# 25k80.net
KiCad netlist of a schematic drawn in EAGLE
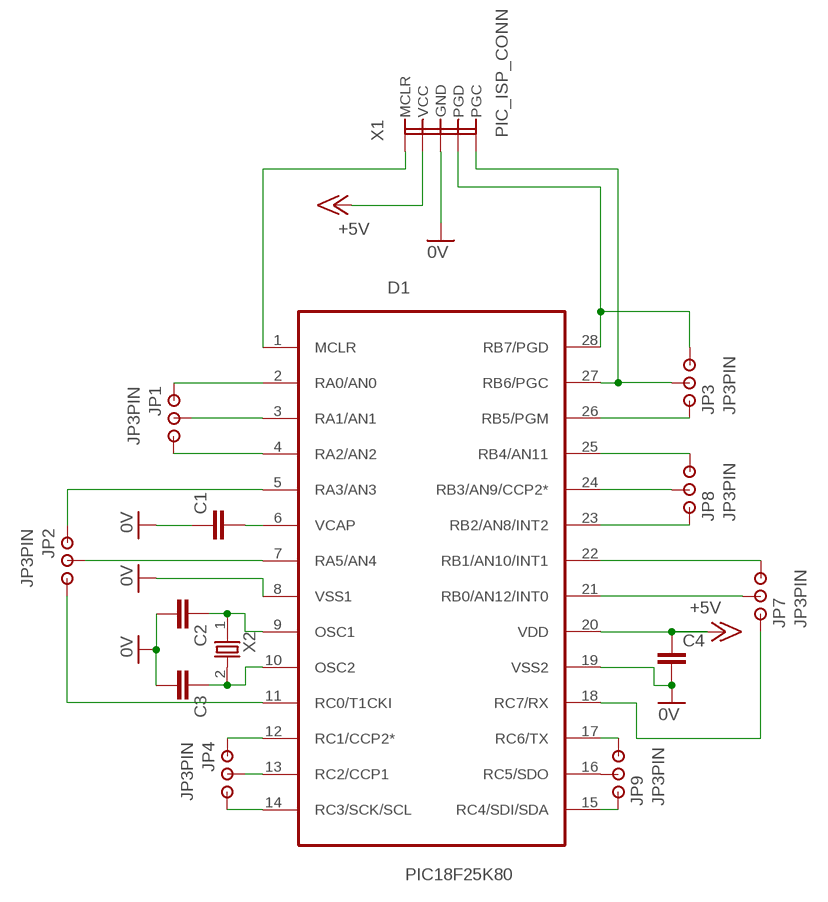
[diagram p0: schematic, sheet 1]

(export (version "E")
  (design (tool "Eeschema 10.0.6"))
  (components
    (comp (ref "C1")
      (value "C0805")
      (footprint "eagle-import:C0805D")
      (libsource (lib "eagle-import") (part "C0805"))
    )
    (comp (ref "C2")
      (value "C0805")
      (footprint "eagle-import:C0805D")
      (libsource (lib "eagle-import") (part "C0805"))
    )
    (comp (ref "C3")
      (value "C0805")
      (footprint "eagle-import:C0805D")
      (libsource (lib "eagle-import") (part "C0805"))
    )
    (comp (ref "C4")
      (value "C0805")
      (footprint "eagle-import:C0805D")
      (libsource (lib "eagle-import") (part "C0805"))
    )
    (comp (ref "D1")
      (value "PIC18F25K80")
      (footprint "eagle-import:SO-28W")
      (libsource (lib "eagle-import") (part "PIC18F25K80"))
    )
    (comp (ref "JP1")
      (value "JP3PIN")
      (footprint "eagle-import:PLC-3PIN")
      (libsource (lib "eagle-import") (part "JP3PIN"))
    )
    (comp (ref "JP2")
      (value "JP3PIN")
      (footprint "eagle-import:PLC-3PIN")
      (libsource (lib "eagle-import") (part "JP3PIN"))
    )
    (comp (ref "JP3")
      (value "JP3PIN")
      (footprint "eagle-import:PLC-3PIN")
      (libsource (lib "eagle-import") (part "JP3PIN"))
    )
    (comp (ref "JP4")
      (value "JP3PIN")
      (footprint "eagle-import:PLC-3PIN")
      (libsource (lib "eagle-import") (part "JP3PIN"))
    )
    (comp (ref "JP7")
      (value "JP3PIN")
      (footprint "eagle-import:PLC-3PIN")
      (libsource (lib "eagle-import") (part "JP3PIN"))
    )
    (comp (ref "JP8")
      (value "JP3PIN")
      (footprint "eagle-import:PLC-3PIN")
      (libsource (lib "eagle-import") (part "JP3PIN"))
    )
    (comp (ref "JP9")
      (value "JP3PIN")
      (footprint "eagle-import:PLC-3PIN")
      (libsource (lib "eagle-import") (part "JP3PIN"))
    )
    (comp (ref "X1")
      (value "PIC_ISP_CONN")
      (footprint "eagle-import:PLC-5PIN")
      (libsource (lib "eagle-import") (part "PIC_ISP_CONN"))
    )
    (comp (ref "X2")
      (value "HC49/S")
      (footprint "eagle-import:HC49_S")
      (libsource (lib "eagle-import") (part "HC49/S"))
    )
  )
  (nets
    (net (code "1") (name "+5V") (class "Default")
      (node (ref "C4") (pin "1") (pinfunction "1_1") (pintype "passive"))
      (node (ref "D1") (pin "20") (pinfunction "VDD_20") (pintype "bidirectional"))
      (node (ref "X1") (pin "P$2") (pinfunction "VCC_P$2") (pintype "bidirectional"))
    )
    (net (code "2") (name "0V") (class "Default")
      (node (ref "C1") (pin "1") (pinfunction "1_1") (pintype "passive"))
      (node (ref "C2") (pin "2") (pinfunction "2_2") (pintype "passive"))
      (node (ref "C3") (pin "2") (pinfunction "2_2") (pintype "passive"))
      (node (ref "C4") (pin "2") (pinfunction "2_2") (pintype "passive"))
      (node (ref "D1") (pin "19") (pinfunction "VSS2_19") (pintype "bidirectional"))
      (node (ref "D1") (pin "8") (pinfunction "VSS1_8") (pintype "bidirectional"))
      (node (ref "X1") (pin "P$3") (pinfunction "GND_P$3") (pintype "bidirectional"))
    )
    (net (code "3") (name "Net-(D1-MCLR)") (class "Default")
      (node (ref "D1") (pin "1") (pinfunction "MCLR_1") (pintype "bidirectional"))
      (node (ref "X1") (pin "P$1") (pinfunction "MCLR_P$1") (pintype "bidirectional"))
    )
    (net (code "4") (name "Net-(D1-OSC1)") (class "Default")
      (node (ref "C2") (pin "1") (pinfunction "1_1") (pintype "passive"))
      (node (ref "D1") (pin "9") (pinfunction "OSC1_9") (pintype "bidirectional"))
      (node (ref "X2") (pin "1") (pinfunction "1_1") (pintype "passive"))
    )
    (net (code "5") (name "Net-(D1-OSC2)") (class "Default")
      (node (ref "C3") (pin "1") (pinfunction "1_1") (pintype "passive"))
      (node (ref "D1") (pin "10") (pinfunction "OSC2_10") (pintype "bidirectional"))
      (node (ref "X2") (pin "2") (pinfunction "2_2") (pintype "passive"))
    )
    (net (code "6") (name "Net-(D1-RA0{slash}AN0)") (class "Default")
      (node (ref "D1") (pin "2") (pinfunction "RA0/AN0_2") (pintype "bidirectional"))
      (node (ref "JP1") (pin "P$1") (pinfunction "P$1_P$1") (pintype "bidirectional"))
    )
    (net (code "7") (name "Net-(D1-RA1{slash}AN1)") (class "Default")
      (node (ref "D1") (pin "3") (pinfunction "RA1/AN1_3") (pintype "bidirectional"))
      (node (ref "JP1") (pin "P$2") (pinfunction "P$2_P$2") (pintype "bidirectional"))
    )
    (net (code "8") (name "Net-(D1-RA2{slash}AN2)") (class "Default")
      (node (ref "D1") (pin "4") (pinfunction "RA2/AN2_4") (pintype "bidirectional"))
      (node (ref "JP1") (pin "P$3") (pinfunction "P$3_P$3") (pintype "bidirectional"))
    )
    (net (code "9") (name "Net-(D1-RA3{slash}AN3)") (class "Default")
      (node (ref "D1") (pin "5") (pinfunction "RA3/AN3_5") (pintype "bidirectional"))
      (node (ref "JP2") (pin "P$1") (pinfunction "P$1_P$1") (pintype "bidirectional"))
    )
    (net (code "10") (name "Net-(D1-RA5{slash}AN4)") (class "Default")
      (node (ref "D1") (pin "7") (pinfunction "RA5/AN4_7") (pintype "bidirectional"))
      (node (ref "JP2") (pin "P$2") (pinfunction "P$2_P$2") (pintype "bidirectional"))
    )
    (net (code "11") (name "Net-(D1-RB0{slash}AN12{slash}INT0)") (class "Default")
      (node (ref "D1") (pin "21") (pinfunction "RB0/AN12/INT0_21") (pintype "bidirectional"))
      (node (ref "JP7") (pin "P$2") (pinfunction "P$2_P$2") (pintype "bidirectional"))
    )
    (net (code "12") (name "Net-(D1-RB1{slash}AN10{slash}INT1)") (class "Default")
      (node (ref "D1") (pin "22") (pinfunction "RB1/AN10/INT1_22") (pintype "bidirectional"))
      (node (ref "JP7") (pin "P$3") (pinfunction "P$3_P$3") (pintype "bidirectional"))
    )
    (net (code "13") (name "Net-(D1-RB2{slash}AN8{slash}INT2)") (class "Default")
      (node (ref "D1") (pin "23") (pinfunction "RB2/AN8/INT2_23") (pintype "bidirectional"))
      (node (ref "JP8") (pin "P$1") (pinfunction "P$1_P$1") (pintype "bidirectional"))
    )
    (net (code "14") (name "Net-(D1-RB3{slash}AN9{slash}CCP2*)") (class "Default")
      (node (ref "D1") (pin "24") (pinfunction "RB3/AN9/CCP2*_24") (pintype "bidirectional"))
      (node (ref "JP8") (pin "P$2") (pinfunction "P$2_P$2") (pintype "bidirectional"))
    )
    (net (code "15") (name "Net-(D1-RB4{slash}AN11)") (class "Default")
      (node (ref "D1") (pin "25") (pinfunction "RB4/AN11_25") (pintype "bidirectional"))
      (node (ref "JP8") (pin "P$3") (pinfunction "P$3_P$3") (pintype "bidirectional"))
    )
    (net (code "16") (name "Net-(D1-RB5{slash}PGM)") (class "Default")
      (node (ref "D1") (pin "26") (pinfunction "RB5/PGM_26") (pintype "bidirectional"))
      (node (ref "JP3") (pin "P$1") (pinfunction "P$1_P$1") (pintype "bidirectional"))
    )
    (net (code "17") (name "Net-(D1-RB6{slash}PGC)") (class "Default")
      (node (ref "D1") (pin "27") (pinfunction "RB6/PGC_27") (pintype "bidirectional"))
      (node (ref "JP3") (pin "P$2") (pinfunction "P$2_P$2") (pintype "bidirectional"))
      (node (ref "X1") (pin "P$5") (pinfunction "PGC_P$5") (pintype "bidirectional"))
    )
    (net (code "18") (name "Net-(D1-RB7{slash}PGD)") (class "Default")
      (node (ref "D1") (pin "28") (pinfunction "RB7/PGD_28") (pintype "bidirectional"))
      (node (ref "JP3") (pin "P$3") (pinfunction "P$3_P$3") (pintype "bidirectional"))
      (node (ref "X1") (pin "P$4") (pinfunction "PGD_P$4") (pintype "bidirectional"))
    )
    (net (code "19") (name "Net-(D1-RC0{slash}T1CKI)") (class "Default")
      (node (ref "D1") (pin "11") (pinfunction "RC0/T1CKI_11") (pintype "bidirectional"))
      (node (ref "JP2") (pin "P$3") (pinfunction "P$3_P$3") (pintype "bidirectional"))
    )
    (net (code "20") (name "Net-(D1-RC1{slash}CCP2*)") (class "Default")
      (node (ref "D1") (pin "12") (pinfunction "RC1/CCP2*_12") (pintype "bidirectional"))
      (node (ref "JP4") (pin "P$1") (pinfunction "P$1_P$1") (pintype "bidirectional"))
    )
    (net (code "21") (name "Net-(D1-RC2{slash}CCP1)") (class "Default")
      (node (ref "D1") (pin "13") (pinfunction "RC2/CCP1_13") (pintype "bidirectional"))
      (node (ref "JP4") (pin "P$2") (pinfunction "P$2_P$2") (pintype "bidirectional"))
    )
    (net (code "22") (name "Net-(D1-RC3{slash}SCK{slash}SCL)") (class "Default")
      (node (ref "D1") (pin "14") (pinfunction "RC3/SCK/SCL_14") (pintype "bidirectional"))
      (node (ref "JP4") (pin "P$3") (pinfunction "P$3_P$3") (pintype "bidirectional"))
    )
    (net (code "23") (name "Net-(D1-RC4{slash}SDI{slash}SDA)") (class "Default")
      (node (ref "D1") (pin "15") (pinfunction "RC4/SDI/SDA_15") (pintype "bidirectional"))
      (node (ref "JP9") (pin "P$1") (pinfunction "P$1_P$1") (pintype "bidirectional"))
    )
    (net (code "24") (name "Net-(D1-RC5{slash}SDO)") (class "Default")
      (node (ref "D1") (pin "16") (pinfunction "RC5/SDO_16") (pintype "bidirectional"))
      (node (ref "JP9") (pin "P$2") (pinfunction "P$2_P$2") (pintype "bidirectional"))
    )
    (net (code "25") (name "Net-(D1-RC6{slash}TX)") (class "Default")
      (node (ref "D1") (pin "17") (pinfunction "RC6/TX_17") (pintype "bidirectional"))
      (node (ref "JP9") (pin "P$3") (pinfunction "P$3_P$3") (pintype "bidirectional"))
    )
    (net (code "26") (name "Net-(D1-RC7{slash}RX)") (class "Default")
      (node (ref "D1") (pin "18") (pinfunction "RC7/RX_18") (pintype "bidirectional"))
      (node (ref "JP7") (pin "P$1") (pinfunction "P$1_P$1") (pintype "bidirectional"))
    )
    (net (code "27") (name "Net-(D1-VCAP)") (class "Default")
      (node (ref "C1") (pin "2") (pinfunction "2_2") (pintype "passive"))
      (node (ref "D1") (pin "6") (pinfunction "VCAP_6") (pintype "bidirectional"))
    )
  )
)
